# SCH_test2_2024-01-14.net
KiCad netlist of a schematic drawn in EasyEDA
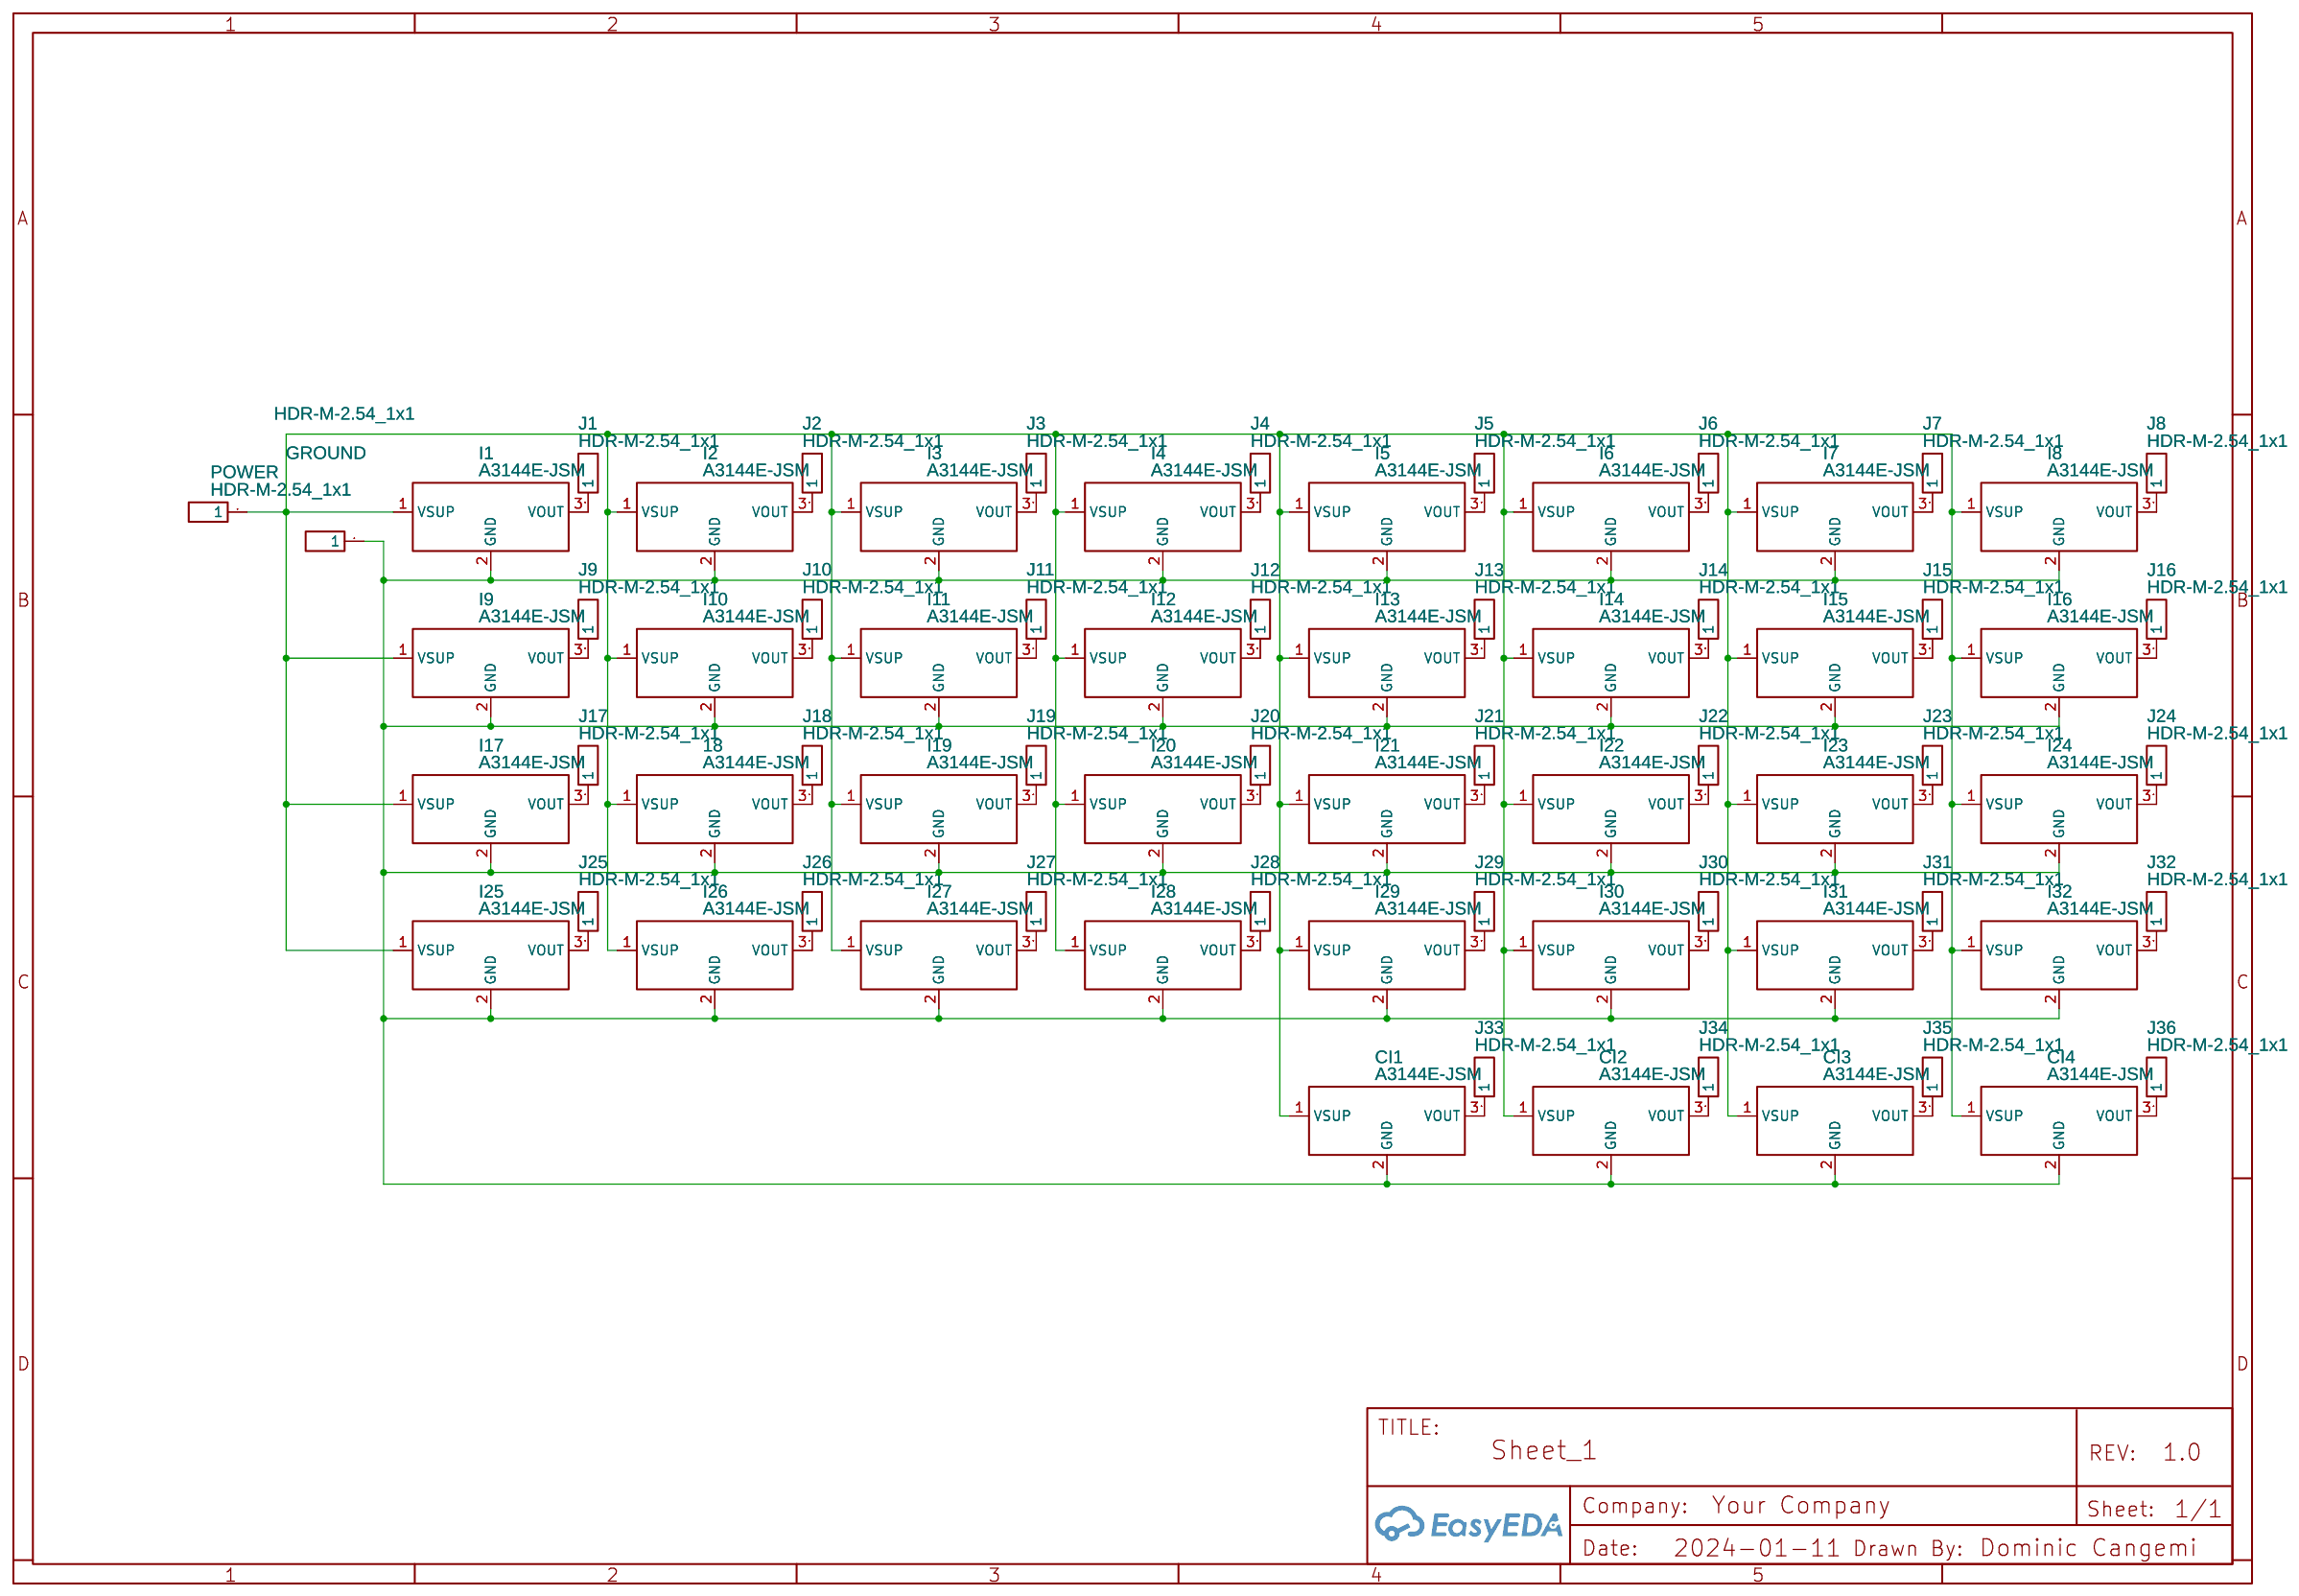
[diagram p0: schematic sheet]

(export (version "E")
  (design (tool "Eeschema 10.0.6"))
  (components
    (comp (ref "18")
      (value "A3144E-JSM")
      (fields (field (name "Manufacturer") "JSMSEMI(杰盛微)"))
      (libsource (lib "") (part "A3144E-JSM_2"))
    )
    (comp (ref "CI1")
      (value "A3144E-JSM")
      (fields (field (name "Manufacturer") "JSMSEMI(杰盛微)"))
      (libsource (lib "") (part "A3144E-JSM_1"))
    )
    (comp (ref "CI2")
      (value "A3144E-JSM")
      (fields (field (name "Manufacturer") "JSMSEMI(杰盛微)"))
      (libsource (lib "") (part "A3144E-JSM_1"))
    )
    (comp (ref "CI3")
      (value "A3144E-JSM")
      (fields (field (name "Manufacturer") "JSMSEMI(杰盛微)"))
      (libsource (lib "") (part "A3144E-JSM_1"))
    )
    (comp (ref "CI4")
      (value "A3144E-JSM")
      (fields (field (name "Manufacturer") "JSMSEMI(杰盛微)"))
      (libsource (lib "") (part "A3144E-JSM_1"))
    )
    (comp (ref "GROUND") (value "HDR-M-2.54_1x1") (libsource (lib "") (part "HDR-M-2.54_1x1_2")))
    (comp (ref "I1")
      (value "A3144E-JSM")
      (fields (field (name "Manufacturer") "JSMSEMI(杰盛微)"))
      (libsource (lib "") (part "A3144E-JSM"))
    )
    (comp (ref "I2")
      (value "A3144E-JSM")
      (fields (field (name "Manufacturer") "JSMSEMI(杰盛微)"))
      (libsource (lib "") (part "A3144E-JSM"))
    )
    (comp (ref "I3")
      (value "A3144E-JSM")
      (fields (field (name "Manufacturer") "JSMSEMI(杰盛微)"))
      (libsource (lib "") (part "A3144E-JSM"))
    )
    (comp (ref "I4")
      (value "A3144E-JSM")
      (fields (field (name "Manufacturer") "JSMSEMI(杰盛微)"))
      (libsource (lib "") (part "A3144E-JSM"))
    )
    (comp (ref "I5")
      (value "A3144E-JSM")
      (fields (field (name "Manufacturer") "JSMSEMI(杰盛微)"))
      (libsource (lib "") (part "A3144E-JSM"))
    )
    (comp (ref "I6")
      (value "A3144E-JSM")
      (fields (field (name "Manufacturer") "JSMSEMI(杰盛微)"))
      (libsource (lib "") (part "A3144E-JSM"))
    )
    (comp (ref "I7")
      (value "A3144E-JSM")
      (fields (field (name "Manufacturer") "JSMSEMI(杰盛微)"))
      (libsource (lib "") (part "A3144E-JSM"))
    )
    (comp (ref "I8")
      (value "A3144E-JSM")
      (fields (field (name "Manufacturer") "JSMSEMI(杰盛微)"))
      (libsource (lib "") (part "A3144E-JSM"))
    )
    (comp (ref "I9")
      (value "A3144E-JSM")
      (fields (field (name "Manufacturer") "JSMSEMI(杰盛微)"))
      (libsource (lib "") (part "A3144E-JSM"))
    )
    (comp (ref "I10")
      (value "A3144E-JSM")
      (fields (field (name "Manufacturer") "JSMSEMI(杰盛微)"))
      (libsource (lib "") (part "A3144E-JSM"))
    )
    (comp (ref "I11")
      (value "A3144E-JSM")
      (fields (field (name "Manufacturer") "JSMSEMI(杰盛微)"))
      (libsource (lib "") (part "A3144E-JSM"))
    )
    (comp (ref "I12")
      (value "A3144E-JSM")
      (fields (field (name "Manufacturer") "JSMSEMI(杰盛微)"))
      (libsource (lib "") (part "A3144E-JSM"))
    )
    (comp (ref "I13")
      (value "A3144E-JSM")
      (fields (field (name "Manufacturer") "JSMSEMI(杰盛微)"))
      (libsource (lib "") (part "A3144E-JSM"))
    )
    (comp (ref "I14")
      (value "A3144E-JSM")
      (fields (field (name "Manufacturer") "JSMSEMI(杰盛微)"))
      (libsource (lib "") (part "A3144E-JSM"))
    )
    (comp (ref "I15")
      (value "A3144E-JSM")
      (fields (field (name "Manufacturer") "JSMSEMI(杰盛微)"))
      (libsource (lib "") (part "A3144E-JSM"))
    )
    (comp (ref "I16")
      (value "A3144E-JSM")
      (fields (field (name "Manufacturer") "JSMSEMI(杰盛微)"))
      (libsource (lib "") (part "A3144E-JSM"))
    )
    (comp (ref "I17")
      (value "A3144E-JSM")
      (fields (field (name "Manufacturer") "JSMSEMI(杰盛微)"))
      (libsource (lib "") (part "A3144E-JSM"))
    )
    (comp (ref "I19")
      (value "A3144E-JSM")
      (fields (field (name "Manufacturer") "JSMSEMI(杰盛微)"))
      (libsource (lib "") (part "A3144E-JSM"))
    )
    (comp (ref "I20")
      (value "A3144E-JSM")
      (fields (field (name "Manufacturer") "JSMSEMI(杰盛微)"))
      (libsource (lib "") (part "A3144E-JSM"))
    )
    (comp (ref "I21")
      (value "A3144E-JSM")
      (fields (field (name "Manufacturer") "JSMSEMI(杰盛微)"))
      (libsource (lib "") (part "A3144E-JSM"))
    )
    (comp (ref "I22")
      (value "A3144E-JSM")
      (fields (field (name "Manufacturer") "JSMSEMI(杰盛微)"))
      (libsource (lib "") (part "A3144E-JSM"))
    )
    (comp (ref "I23")
      (value "A3144E-JSM")
      (fields (field (name "Manufacturer") "JSMSEMI(杰盛微)"))
      (libsource (lib "") (part "A3144E-JSM"))
    )
    (comp (ref "I24")
      (value "A3144E-JSM")
      (fields (field (name "Manufacturer") "JSMSEMI(杰盛微)"))
      (libsource (lib "") (part "A3144E-JSM"))
    )
    (comp (ref "I25")
      (value "A3144E-JSM")
      (fields (field (name "Manufacturer") "JSMSEMI(杰盛微)"))
      (libsource (lib "") (part "A3144E-JSM"))
    )
    (comp (ref "I26")
      (value "A3144E-JSM")
      (fields (field (name "Manufacturer") "JSMSEMI(杰盛微)"))
      (libsource (lib "") (part "A3144E-JSM"))
    )
    (comp (ref "I27")
      (value "A3144E-JSM")
      (fields (field (name "Manufacturer") "JSMSEMI(杰盛微)"))
      (libsource (lib "") (part "A3144E-JSM"))
    )
    (comp (ref "I28")
      (value "A3144E-JSM")
      (fields (field (name "Manufacturer") "JSMSEMI(杰盛微)"))
      (libsource (lib "") (part "A3144E-JSM"))
    )
    (comp (ref "I29")
      (value "A3144E-JSM")
      (fields (field (name "Manufacturer") "JSMSEMI(杰盛微)"))
      (libsource (lib "") (part "A3144E-JSM"))
    )
    (comp (ref "I30")
      (value "A3144E-JSM")
      (fields (field (name "Manufacturer") "JSMSEMI(杰盛微)"))
      (libsource (lib "") (part "A3144E-JSM"))
    )
    (comp (ref "I31")
      (value "A3144E-JSM")
      (fields (field (name "Manufacturer") "JSMSEMI(杰盛微)"))
      (libsource (lib "") (part "A3144E-JSM"))
    )
    (comp (ref "I32")
      (value "A3144E-JSM")
      (fields (field (name "Manufacturer") "JSMSEMI(杰盛微)"))
      (libsource (lib "") (part "A3144E-JSM"))
    )
    (comp (ref "J1") (value "HDR-M-2.54_1x1") (libsource (lib "") (part "HDR-M-2.54_1x1")))
    (comp (ref "J2") (value "HDR-M-2.54_1x1") (libsource (lib "") (part "HDR-M-2.54_1x1")))
    (comp (ref "J3") (value "HDR-M-2.54_1x1") (libsource (lib "") (part "HDR-M-2.54_1x1")))
    (comp (ref "J4") (value "HDR-M-2.54_1x1") (libsource (lib "") (part "HDR-M-2.54_1x1")))
    (comp (ref "J5") (value "HDR-M-2.54_1x1") (libsource (lib "") (part "HDR-M-2.54_1x1")))
    (comp (ref "J6") (value "HDR-M-2.54_1x1") (libsource (lib "") (part "HDR-M-2.54_1x1")))
    (comp (ref "J7") (value "HDR-M-2.54_1x1") (libsource (lib "") (part "HDR-M-2.54_1x1")))
    (comp (ref "J8") (value "HDR-M-2.54_1x1") (libsource (lib "") (part "HDR-M-2.54_1x1")))
    (comp (ref "J9") (value "HDR-M-2.54_1x1") (libsource (lib "") (part "HDR-M-2.54_1x1")))
    (comp (ref "J10") (value "HDR-M-2.54_1x1") (libsource (lib "") (part "HDR-M-2.54_1x1")))
    (comp (ref "J11") (value "HDR-M-2.54_1x1") (libsource (lib "") (part "HDR-M-2.54_1x1")))
    (comp (ref "J12") (value "HDR-M-2.54_1x1") (libsource (lib "") (part "HDR-M-2.54_1x1")))
    (comp (ref "J13") (value "HDR-M-2.54_1x1") (libsource (lib "") (part "HDR-M-2.54_1x1")))
    (comp (ref "J14") (value "HDR-M-2.54_1x1") (libsource (lib "") (part "HDR-M-2.54_1x1")))
    (comp (ref "J15") (value "HDR-M-2.54_1x1") (libsource (lib "") (part "HDR-M-2.54_1x1")))
    (comp (ref "J16") (value "HDR-M-2.54_1x1") (libsource (lib "") (part "HDR-M-2.54_1x1")))
    (comp (ref "J17") (value "HDR-M-2.54_1x1") (libsource (lib "") (part "HDR-M-2.54_1x1")))
    (comp (ref "J18") (value "HDR-M-2.54_1x1") (libsource (lib "") (part "HDR-M-2.54_1x1")))
    (comp (ref "J19") (value "HDR-M-2.54_1x1") (libsource (lib "") (part "HDR-M-2.54_1x1")))
    (comp (ref "J20") (value "HDR-M-2.54_1x1") (libsource (lib "") (part "HDR-M-2.54_1x1")))
    (comp (ref "J21") (value "HDR-M-2.54_1x1") (libsource (lib "") (part "HDR-M-2.54_1x1")))
    (comp (ref "J22") (value "HDR-M-2.54_1x1") (libsource (lib "") (part "HDR-M-2.54_1x1")))
    (comp (ref "J23") (value "HDR-M-2.54_1x1") (libsource (lib "") (part "HDR-M-2.54_1x1")))
    (comp (ref "J24") (value "HDR-M-2.54_1x1") (libsource (lib "") (part "HDR-M-2.54_1x1")))
    (comp (ref "J25") (value "HDR-M-2.54_1x1") (libsource (lib "") (part "HDR-M-2.54_1x1")))
    (comp (ref "J26") (value "HDR-M-2.54_1x1") (libsource (lib "") (part "HDR-M-2.54_1x1")))
    (comp (ref "J27") (value "HDR-M-2.54_1x1") (libsource (lib "") (part "HDR-M-2.54_1x1")))
    (comp (ref "J28") (value "HDR-M-2.54_1x1") (libsource (lib "") (part "HDR-M-2.54_1x1")))
    (comp (ref "J29") (value "HDR-M-2.54_1x1") (libsource (lib "") (part "HDR-M-2.54_1x1")))
    (comp (ref "J30") (value "HDR-M-2.54_1x1") (libsource (lib "") (part "HDR-M-2.54_1x1")))
    (comp (ref "J31") (value "HDR-M-2.54_1x1") (libsource (lib "") (part "HDR-M-2.54_1x1")))
    (comp (ref "J32") (value "HDR-M-2.54_1x1") (libsource (lib "") (part "HDR-M-2.54_1x1")))
    (comp (ref "J33") (value "HDR-M-2.54_1x1") (libsource (lib "") (part "HDR-M-2.54_1x1")))
    (comp (ref "J34") (value "HDR-M-2.54_1x1") (libsource (lib "") (part "HDR-M-2.54_1x1")))
    (comp (ref "J35") (value "HDR-M-2.54_1x1") (libsource (lib "") (part "HDR-M-2.54_1x1")))
    (comp (ref "J36") (value "HDR-M-2.54_1x1") (libsource (lib "") (part "HDR-M-2.54_1x1")))
    (comp (ref "POWER") (value "HDR-M-2.54_1x1") (libsource (lib "") (part "HDR-M-2.54_1x1_1")))
  )
  (nets
    (net (code "1") (name "Net-(18-GND)") (class "Default")
      (node (ref "18") (pin "2") (pinfunction "GND_2") (pintype "unspecified"))
      (node (ref "CI1") (pin "2") (pinfunction "GND_2") (pintype "unspecified"))
      (node (ref "CI2") (pin "2") (pinfunction "GND_2") (pintype "unspecified"))
      (node (ref "CI3") (pin "2") (pinfunction "GND_2") (pintype "unspecified"))
      (node (ref "CI4") (pin "2") (pinfunction "GND_2") (pintype "unspecified"))
      (node (ref "GROUND") (pin "1") (pinfunction "1_1") (pintype "input"))
      (node (ref "I1") (pin "2") (pinfunction "GND_2") (pintype "unspecified"))
      (node (ref "I10") (pin "2") (pinfunction "GND_2") (pintype "unspecified"))
      (node (ref "I11") (pin "2") (pinfunction "GND_2") (pintype "unspecified"))
      (node (ref "I12") (pin "2") (pinfunction "GND_2") (pintype "unspecified"))
      (node (ref "I13") (pin "2") (pinfunction "GND_2") (pintype "unspecified"))
      (node (ref "I14") (pin "2") (pinfunction "GND_2") (pintype "unspecified"))
      (node (ref "I15") (pin "2") (pinfunction "GND_2") (pintype "unspecified"))
      (node (ref "I16") (pin "2") (pinfunction "GND_2") (pintype "unspecified"))
      (node (ref "I17") (pin "2") (pinfunction "GND_2") (pintype "unspecified"))
      (node (ref "I19") (pin "2") (pinfunction "GND_2") (pintype "unspecified"))
      (node (ref "I2") (pin "2") (pinfunction "GND_2") (pintype "unspecified"))
      (node (ref "I20") (pin "2") (pinfunction "GND_2") (pintype "unspecified"))
      (node (ref "I21") (pin "2") (pinfunction "GND_2") (pintype "unspecified"))
      (node (ref "I22") (pin "2") (pinfunction "GND_2") (pintype "unspecified"))
      (node (ref "I23") (pin "2") (pinfunction "GND_2") (pintype "unspecified"))
      (node (ref "I24") (pin "2") (pinfunction "GND_2") (pintype "unspecified"))
      (node (ref "I25") (pin "2") (pinfunction "GND_2") (pintype "unspecified"))
      (node (ref "I26") (pin "2") (pinfunction "GND_2") (pintype "unspecified"))
      (node (ref "I27") (pin "2") (pinfunction "GND_2") (pintype "unspecified"))
      (node (ref "I28") (pin "2") (pinfunction "GND_2") (pintype "unspecified"))
      (node (ref "I29") (pin "2") (pinfunction "GND_2") (pintype "unspecified"))
      (node (ref "I3") (pin "2") (pinfunction "GND_2") (pintype "unspecified"))
      (node (ref "I30") (pin "2") (pinfunction "GND_2") (pintype "unspecified"))
      (node (ref "I31") (pin "2") (pinfunction "GND_2") (pintype "unspecified"))
      (node (ref "I32") (pin "2") (pinfunction "GND_2") (pintype "unspecified"))
      (node (ref "I4") (pin "2") (pinfunction "GND_2") (pintype "unspecified"))
      (node (ref "I5") (pin "2") (pinfunction "GND_2") (pintype "unspecified"))
      (node (ref "I6") (pin "2") (pinfunction "GND_2") (pintype "unspecified"))
      (node (ref "I7") (pin "2") (pinfunction "GND_2") (pintype "unspecified"))
      (node (ref "I8") (pin "2") (pinfunction "GND_2") (pintype "unspecified"))
      (node (ref "I9") (pin "2") (pinfunction "GND_2") (pintype "unspecified"))
    )
    (net (code "2") (name "Net-(18-VOUT)") (class "Default")
      (node (ref "18") (pin "3") (pinfunction "VOUT_3") (pintype "unspecified"))
      (node (ref "J18") (pin "1") (pinfunction "1_1") (pintype "input"))
    )
    (net (code "3") (name "Net-(18-VSUP)") (class "Default")
      (node (ref "18") (pin "1") (pinfunction "VSUP_1") (pintype "unspecified"))
      (node (ref "CI1") (pin "1") (pinfunction "VSUP_1") (pintype "unspecified"))
      (node (ref "CI2") (pin "1") (pinfunction "VSUP_1") (pintype "unspecified"))
      (node (ref "CI3") (pin "1") (pinfunction "VSUP_1") (pintype "unspecified"))
      (node (ref "CI4") (pin "1") (pinfunction "VSUP_1") (pintype "unspecified"))
      (node (ref "I1") (pin "1") (pinfunction "VSUP_1") (pintype "unspecified"))
      (node (ref "I10") (pin "1") (pinfunction "VSUP_1") (pintype "unspecified"))
      (node (ref "I11") (pin "1") (pinfunction "VSUP_1") (pintype "unspecified"))
      (node (ref "I12") (pin "1") (pinfunction "VSUP_1") (pintype "unspecified"))
      (node (ref "I13") (pin "1") (pinfunction "VSUP_1") (pintype "unspecified"))
      (node (ref "I14") (pin "1") (pinfunction "VSUP_1") (pintype "unspecified"))
      (node (ref "I15") (pin "1") (pinfunction "VSUP_1") (pintype "unspecified"))
      (node (ref "I16") (pin "1") (pinfunction "VSUP_1") (pintype "unspecified"))
      (node (ref "I17") (pin "1") (pinfunction "VSUP_1") (pintype "unspecified"))
      (node (ref "I19") (pin "1") (pinfunction "VSUP_1") (pintype "unspecified"))
      (node (ref "I2") (pin "1") (pinfunction "VSUP_1") (pintype "unspecified"))
      (node (ref "I20") (pin "1") (pinfunction "VSUP_1") (pintype "unspecified"))
      (node (ref "I21") (pin "1") (pinfunction "VSUP_1") (pintype "unspecified"))
      (node (ref "I22") (pin "1") (pinfunction "VSUP_1") (pintype "unspecified"))
      (node (ref "I23") (pin "1") (pinfunction "VSUP_1") (pintype "unspecified"))
      (node (ref "I24") (pin "1") (pinfunction "VSUP_1") (pintype "unspecified"))
      (node (ref "I25") (pin "1") (pinfunction "VSUP_1") (pintype "unspecified"))
      (node (ref "I26") (pin "1") (pinfunction "VSUP_1") (pintype "unspecified"))
      (node (ref "I27") (pin "1") (pinfunction "VSUP_1") (pintype "unspecified"))
      (node (ref "I28") (pin "1") (pinfunction "VSUP_1") (pintype "unspecified"))
      (node (ref "I29") (pin "1") (pinfunction "VSUP_1") (pintype "unspecified"))
      (node (ref "I3") (pin "1") (pinfunction "VSUP_1") (pintype "unspecified"))
      (node (ref "I30") (pin "1") (pinfunction "VSUP_1") (pintype "unspecified"))
      (node (ref "I31") (pin "1") (pinfunction "VSUP_1") (pintype "unspecified"))
      (node (ref "I32") (pin "1") (pinfunction "VSUP_1") (pintype "unspecified"))
      (node (ref "I4") (pin "1") (pinfunction "VSUP_1") (pintype "unspecified"))
      (node (ref "I5") (pin "1") (pinfunction "VSUP_1") (pintype "unspecified"))
      (node (ref "I6") (pin "1") (pinfunction "VSUP_1") (pintype "unspecified"))
      (node (ref "I7") (pin "1") (pinfunction "VSUP_1") (pintype "unspecified"))
      (node (ref "I8") (pin "1") (pinfunction "VSUP_1") (pintype "unspecified"))
      (node (ref "I9") (pin "1") (pinfunction "VSUP_1") (pintype "unspecified"))
      (node (ref "POWER") (pin "1") (pinfunction "1_1") (pintype "input"))
    )
    (net (code "4") (name "Net-(CI1-VOUT)") (class "Default")
      (node (ref "CI1") (pin "3") (pinfunction "VOUT_3") (pintype "unspecified"))
      (node (ref "J33") (pin "1") (pinfunction "1_1") (pintype "input"))
    )
    (net (code "5") (name "Net-(CI2-VOUT)") (class "Default")
      (node (ref "CI2") (pin "3") (pinfunction "VOUT_3") (pintype "unspecified"))
      (node (ref "J34") (pin "1") (pinfunction "1_1") (pintype "input"))
    )
    (net (code "6") (name "Net-(CI3-VOUT)") (class "Default")
      (node (ref "CI3") (pin "3") (pinfunction "VOUT_3") (pintype "unspecified"))
      (node (ref "J35") (pin "1") (pinfunction "1_1") (pintype "input"))
    )
    (net (code "7") (name "Net-(CI4-VOUT)") (class "Default")
      (node (ref "CI4") (pin "3") (pinfunction "VOUT_3") (pintype "unspecified"))
      (node (ref "J36") (pin "1") (pinfunction "1_1") (pintype "input"))
    )
    (net (code "8") (name "Net-(I1-VOUT)") (class "Default")
      (node (ref "I1") (pin "3") (pinfunction "VOUT_3") (pintype "unspecified"))
      (node (ref "J1") (pin "1") (pinfunction "1_1") (pintype "input"))
    )
    (net (code "9") (name "Net-(I2-VOUT)") (class "Default")
      (node (ref "I2") (pin "3") (pinfunction "VOUT_3") (pintype "unspecified"))
      (node (ref "J2") (pin "1") (pinfunction "1_1") (pintype "input"))
    )
    (net (code "10") (name "Net-(I3-VOUT)") (class "Default")
      (node (ref "I3") (pin "3") (pinfunction "VOUT_3") (pintype "unspecified"))
      (node (ref "J3") (pin "1") (pinfunction "1_1") (pintype "input"))
    )
    (net (code "11") (name "Net-(I4-VOUT)") (class "Default")
      (node (ref "I4") (pin "3") (pinfunction "VOUT_3") (pintype "unspecified"))
      (node (ref "J4") (pin "1") (pinfunction "1_1") (pintype "input"))
    )
    (net (code "12") (name "Net-(I5-VOUT)") (class "Default")
      (node (ref "I5") (pin "3") (pinfunction "VOUT_3") (pintype "unspecified"))
      (node (ref "J5") (pin "1") (pinfunction "1_1") (pintype "input"))
    )
    (net (code "13") (name "Net-(I6-VOUT)") (class "Default")
      (node (ref "I6") (pin "3") (pinfunction "VOUT_3") (pintype "unspecified"))
      (node (ref "J6") (pin "1") (pinfunction "1_1") (pintype "input"))
    )
    (net (code "14") (name "Net-(I7-VOUT)") (class "Default")
      (node (ref "I7") (pin "3") (pinfunction "VOUT_3") (pintype "unspecified"))
      (node (ref "J7") (pin "1") (pinfunction "1_1") (pintype "input"))
    )
    (net (code "15") (name "Net-(I8-VOUT)") (class "Default")
      (node (ref "I8") (pin "3") (pinfunction "VOUT_3") (pintype "unspecified"))
      (node (ref "J8") (pin "1") (pinfunction "1_1") (pintype "input"))
    )
    (net (code "16") (name "Net-(I9-VOUT)") (class "Default")
      (node (ref "I9") (pin "3") (pinfunction "VOUT_3") (pintype "unspecified"))
      (node (ref "J9") (pin "1") (pinfunction "1_1") (pintype "input"))
    )
    (net (code "17") (name "Net-(I10-VOUT)") (class "Default")
      (node (ref "I10") (pin "3") (pinfunction "VOUT_3") (pintype "unspecified"))
      (node (ref "J10") (pin "1") (pinfunction "1_1") (pintype "input"))
    )
    (net (code "18") (name "Net-(I11-VOUT)") (class "Default")
      (node (ref "I11") (pin "3") (pinfunction "VOUT_3") (pintype "unspecified"))
      (node (ref "J11") (pin "1") (pinfunction "1_1") (pintype "input"))
    )
    (net (code "19") (name "Net-(I12-VOUT)") (class "Default")
      (node (ref "I12") (pin "3") (pinfunction "VOUT_3") (pintype "unspecified"))
      (node (ref "J12") (pin "1") (pinfunction "1_1") (pintype "input"))
    )
    (net (code "20") (name "Net-(I13-VOUT)") (class "Default")
      (node (ref "I13") (pin "3") (pinfunction "VOUT_3") (pintype "unspecified"))
      (node (ref "J13") (pin "1") (pinfunction "1_1") (pintype "input"))
    )
    (net (code "21") (name "Net-(I14-VOUT)") (class "Default")
      (node (ref "I14") (pin "3") (pinfunction "VOUT_3") (pintype "unspecified"))
      (node (ref "J14") (pin "1") (pinfunction "1_1") (pintype "input"))
    )
    (net (code "22") (name "Net-(I15-VOUT)") (class "Default")
      (node (ref "I15") (pin "3") (pinfunction "VOUT_3") (pintype "unspecified"))
      (node (ref "J15") (pin "1") (pinfunction "1_1") (pintype "input"))
    )
    (net (code "23") (name "Net-(I16-VOUT)") (class "Default")
      (node (ref "I16") (pin "3") (pinfunction "VOUT_3") (pintype "unspecified"))
      (node (ref "J16") (pin "1") (pinfunction "1_1") (pintype "input"))
    )
    (net (code "24") (name "Net-(I17-VOUT)") (class "Default")
      (node (ref "I17") (pin "3") (pinfunction "VOUT_3") (pintype "unspecified"))
      (node (ref "J17") (pin "1") (pinfunction "1_1") (pintype "input"))
    )
    (net (code "25") (name "Net-(I19-VOUT)") (class "Default")
      (node (ref "I19") (pin "3") (pinfunction "VOUT_3") (pintype "unspecified"))
      (node (ref "J19") (pin "1") (pinfunction "1_1") (pintype "input"))
    )
    (net (code "26") (name "Net-(I20-VOUT)") (class "Default")
      (node (ref "I20") (pin "3") (pinfunction "VOUT_3") (pintype "unspecified"))
      (node (ref "J20") (pin "1") (pinfunction "1_1") (pintype "input"))
    )
    (net (code "27") (name "Net-(I21-VOUT)") (class "Default")
      (node (ref "I21") (pin "3") (pinfunction "VOUT_3") (pintype "unspecified"))
      (node (ref "J21") (pin "1") (pinfunction "1_1") (pintype "input"))
    )
    (net (code "28") (name "Net-(I22-VOUT)") (class "Default")
      (node (ref "I22") (pin "3") (pinfunction "VOUT_3") (pintype "unspecified"))
      (node (ref "J22") (pin "1") (pinfunction "1_1") (pintype "input"))
    )
    (net (code "29") (name "Net-(I23-VOUT)") (class "Default")
      (node (ref "I23") (pin "3") (pinfunction "VOUT_3") (pintype "unspecified"))
      (node (ref "J23") (pin "1") (pinfunction "1_1") (pintype "input"))
    )
    (net (code "30") (name "Net-(I24-VOUT)") (class "Default")
      (node (ref "I24") (pin "3") (pinfunction "VOUT_3") (pintype "unspecified"))
      (node (ref "J24") (pin "1") (pinfunction "1_1") (pintype "input"))
    )
    (net (code "31") (name "Net-(I25-VOUT)") (class "Default")
      (node (ref "I25") (pin "3") (pinfunction "VOUT_3") (pintype "unspecified"))
      (node (ref "J25") (pin "1") (pinfunction "1_1") (pintype "input"))
    )
    (net (code "32") (name "Net-(I26-VOUT)") (class "Default")
      (node (ref "I26") (pin "3") (pinfunction "VOUT_3") (pintype "unspecified"))
      (node (ref "J26") (pin "1") (pinfunction "1_1") (pintype "input"))
    )
    (net (code "33") (name "Net-(I27-VOUT)") (class "Default")
      (node (ref "I27") (pin "3") (pinfunction "VOUT_3") (pintype "unspecified"))
      (node (ref "J27") (pin "1") (pinfunction "1_1") (pintype "input"))
    )
    (net (code "34") (name "Net-(I28-VOUT)") (class "Default")
      (node (ref "I28") (pin "3") (pinfunction "VOUT_3") (pintype "unspecified"))
      (node (ref "J28") (pin "1") (pinfunction "1_1") (pintype "input"))
    )
    (net (code "35") (name "Net-(I29-VOUT)") (class "Default")
      (node (ref "I29") (pin "3") (pinfunction "VOUT_3") (pintype "unspecified"))
      (node (ref "J29") (pin "1") (pinfunction "1_1") (pintype "input"))
    )
    (net (code "36") (name "Net-(I30-VOUT)") (class "Default")
      (node (ref "I30") (pin "3") (pinfunction "VOUT_3") (pintype "unspecified"))
      (node (ref "J30") (pin "1") (pinfunction "1_1") (pintype "input"))
    )
    (net (code "37") (name "Net-(I31-VOUT)") (class "Default")
      (node (ref "I31") (pin "3") (pinfunction "VOUT_3") (pintype "unspecified"))
      (node (ref "J31") (pin "1") (pinfunction "1_1") (pintype "input"))
    )
    (net (code "38") (name "Net-(I32-VOUT)") (class "Default")
      (node (ref "I32") (pin "3") (pinfunction "VOUT_3") (pintype "unspecified"))
      (node (ref "J32") (pin "1") (pinfunction "1_1") (pintype "input"))
    )
  )
)
